# uknc_fdd2sd_rev1.net
KiCad netlist of a schematic drawn in EAGLE
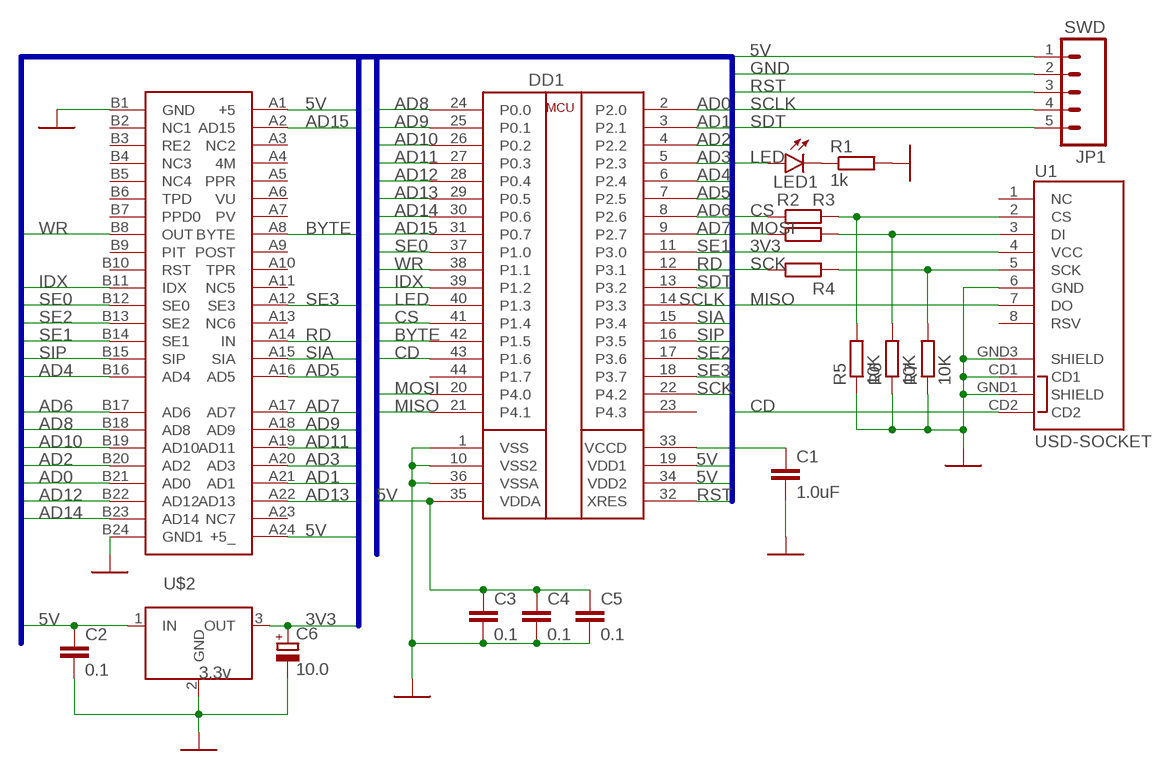
[diagram p0: schematic, sheet 1]

(export (version "E")
  (design (tool "Eeschema 10.0.6"))
  (components
    (comp (ref "C1")
      (value "1.0uF")
      (footprint "eagle-import:0805-CAP")
      (libsource (lib "eagle-import") (part "1.0UF-25V-+80/-20(0805){dblquote}"))
    )
    (comp (ref "C2")
      (value "0.1")
      (footprint "eagle-import:C0805")
      (libsource (lib "eagle-import") (part "C-EUC0805"))
    )
    (comp (ref "C3")
      (value "0.1")
      (footprint "eagle-import:C0805")
      (libsource (lib "eagle-import") (part "C-EUC0805"))
    )
    (comp (ref "C4")
      (value "0.1")
      (footprint "eagle-import:C0805")
      (libsource (lib "eagle-import") (part "C-EUC0805"))
    )
    (comp (ref "C5")
      (value "0.1")
      (footprint "eagle-import:C0805")
      (libsource (lib "eagle-import") (part "C-EUC0805"))
    )
    (comp (ref "C6")
      (value "10.0")
      (footprint "eagle-import:E1,8-4")
      (libsource (lib "eagle-import") (part "CPOL-EUE1.8-4"))
    )
    (comp (ref "DD1")
      (value "CY8C4245AXI")
      (footprint "eagle-import:TQFP-44")
      (libsource (lib "eagle-import") (part "CY8C4245AXI"))
    )
    (comp (ref "JP1")
      (value "SWD")
      (footprint "eagle-import:1X05")
      (libsource (lib "eagle-import") (part "M05PTH"))
    )
    (comp (ref "LED1")
      (value "LED1206")
      (footprint "eagle-import:LED-1206")
      (libsource (lib "eagle-import") (part "LED1206"))
    )
    (comp (ref "R1")
      (value "1k")
      (footprint "eagle-import:R0805")
      (libsource (lib "eagle-import") (part "R-EU_R0805"))
    )
    (comp (ref "R2")
      (value "R-EU_R0805")
      (footprint "eagle-import:R0805")
      (libsource (lib "eagle-import") (part "R-EU_R0805"))
    )
    (comp (ref "R3")
      (value "R-EU_R0805")
      (footprint "eagle-import:R0805")
      (libsource (lib "eagle-import") (part "R-EU_R0805"))
    )
    (comp (ref "R4")
      (value "R-EU_R0805")
      (footprint "eagle-import:R0805")
      (libsource (lib "eagle-import") (part "R-EU_R0805"))
    )
    (comp (ref "R5")
      (value "10K")
      (footprint "eagle-import:M0805")
      (libsource (lib "eagle-import") (part "R-EU_M0805"))
    )
    (comp (ref "R6")
      (value "10K")
      (footprint "eagle-import:M0805")
      (libsource (lib "eagle-import") (part "R-EU_M0805"))
    )
    (comp (ref "R7")
      (value "10K")
      (footprint "eagle-import:M0805")
      (libsource (lib "eagle-import") (part "R-EU_M0805"))
    )
    (comp (ref "U$1")
      (value "SNP")
      (footprint "eagle-import:SNP15-48-BOARD")
      (libsource (lib "eagle-import") (part "SNP"))
    )
    (comp (ref "U$2")
      (value "3.3v")
      (footprint "eagle-import:1235B")
      (libsource (lib "eagle-import") (part "1235B"))
    )
    (comp (ref "U1")
      (value "USD-SOCKET")
      (footprint "eagle-import:MICROSD_1_1")
      (libsource (lib "eagle-import") (part "USD-SOCKET"))
    )
  )
  (nets
    (net (code "1") (name "/3V3") (class "Default")
      (node (ref "C6") (pin "+") (pinfunction "+_+") (pintype "passive"))
      (node (ref "U$2") (pin "3") (pinfunction "OUT_3") (pintype "bidirectional"))
      (node (ref "U1") (pin "4") (pinfunction "VCC_4") (pintype "bidirectional"))
    )
    (net (code "2") (name "/5V") (class "Default")
      (node (ref "C2") (pin "1") (pinfunction "1_1") (pintype "passive"))
      (node (ref "C3") (pin "1") (pinfunction "1_1") (pintype "passive"))
      (node (ref "C4") (pin "1") (pinfunction "1_1") (pintype "passive"))
      (node (ref "C5") (pin "1") (pinfunction "1_1") (pintype "passive"))
      (node (ref "DD1") (pin "19") (pinfunction "VDD1_19") (pintype "bidirectional"))
      (node (ref "DD1") (pin "34") (pinfunction "VDD2_34") (pintype "bidirectional"))
      (node (ref "DD1") (pin "35") (pinfunction "VDDA_35") (pintype "bidirectional"))
      (node (ref "JP1") (pin "1") (pinfunction "1_1") (pintype "passive"))
      (node (ref "U$1") (pin "A1") (pinfunction "+5_A1") (pintype "bidirectional"))
      (node (ref "U$1") (pin "A24") (pinfunction "+5__A24") (pintype "bidirectional"))
      (node (ref "U$2") (pin "1") (pinfunction "IN_1") (pintype "bidirectional"))
    )
    (net (code "3") (name "/AD0") (class "Default")
      (node (ref "DD1") (pin "2") (pinfunction "P2.0_2") (pintype "bidirectional"))
      (node (ref "U$1") (pin "B21") (pinfunction "AD0_B21") (pintype "bidirectional"))
    )
    (net (code "4") (name "/AD1") (class "Default")
      (node (ref "DD1") (pin "3") (pinfunction "P2.1_3") (pintype "bidirectional"))
      (node (ref "U$1") (pin "A21") (pinfunction "AD1_A21") (pintype "bidirectional"))
    )
    (net (code "5") (name "/AD2") (class "Default")
      (node (ref "DD1") (pin "4") (pinfunction "P2.2_4") (pintype "bidirectional"))
      (node (ref "U$1") (pin "B20") (pinfunction "AD2_B20") (pintype "bidirectional"))
    )
    (net (code "6") (name "/AD3") (class "Default")
      (node (ref "DD1") (pin "5") (pinfunction "P2.3_5") (pintype "bidirectional"))
      (node (ref "U$1") (pin "A20") (pinfunction "AD3_A20") (pintype "bidirectional"))
    )
    (net (code "7") (name "/AD4") (class "Default")
      (node (ref "DD1") (pin "6") (pinfunction "P2.4_6") (pintype "bidirectional"))
      (node (ref "U$1") (pin "B16") (pinfunction "AD4_B16") (pintype "bidirectional"))
    )
    (net (code "8") (name "/AD5") (class "Default")
      (node (ref "DD1") (pin "7") (pinfunction "P2.5_7") (pintype "bidirectional"))
      (node (ref "U$1") (pin "A16") (pinfunction "AD5_A16") (pintype "bidirectional"))
    )
    (net (code "9") (name "/AD6") (class "Default")
      (node (ref "DD1") (pin "8") (pinfunction "P2.6_8") (pintype "bidirectional"))
      (node (ref "U$1") (pin "B17") (pinfunction "AD6_B17") (pintype "bidirectional"))
    )
    (net (code "10") (name "/AD7") (class "Default")
      (node (ref "DD1") (pin "9") (pinfunction "P2.7_9") (pintype "bidirectional"))
      (node (ref "U$1") (pin "A17") (pinfunction "AD7_A17") (pintype "bidirectional"))
    )
    (net (code "11") (name "/AD8") (class "Default")
      (node (ref "DD1") (pin "24") (pinfunction "P0.0_24") (pintype "bidirectional"))
      (node (ref "U$1") (pin "B18") (pinfunction "AD8_B18") (pintype "bidirectional"))
    )
    (net (code "12") (name "/AD9") (class "Default")
      (node (ref "DD1") (pin "25") (pinfunction "P0.1_25") (pintype "bidirectional"))
      (node (ref "U$1") (pin "A18") (pinfunction "AD9_A18") (pintype "bidirectional"))
    )
    (net (code "13") (name "/AD10") (class "Default")
      (node (ref "DD1") (pin "26") (pinfunction "P0.2_26") (pintype "bidirectional"))
      (node (ref "U$1") (pin "B19") (pinfunction "AD10_B19") (pintype "bidirectional"))
    )
    (net (code "14") (name "/AD11") (class "Default")
      (node (ref "DD1") (pin "27") (pinfunction "P0.3_27") (pintype "bidirectional"))
      (node (ref "U$1") (pin "A19") (pinfunction "AD11_A19") (pintype "bidirectional"))
    )
    (net (code "15") (name "/AD12") (class "Default")
      (node (ref "DD1") (pin "28") (pinfunction "P0.4_28") (pintype "bidirectional"))
      (node (ref "U$1") (pin "B22") (pinfunction "AD12_B22") (pintype "bidirectional"))
    )
    (net (code "16") (name "/AD13") (class "Default")
      (node (ref "DD1") (pin "29") (pinfunction "P0.5_29") (pintype "bidirectional"))
      (node (ref "U$1") (pin "A22") (pinfunction "AD13_A22") (pintype "bidirectional"))
    )
    (net (code "17") (name "/AD14") (class "Default")
      (node (ref "DD1") (pin "30") (pinfunction "P0.6_30") (pintype "bidirectional"))
      (node (ref "U$1") (pin "B23") (pinfunction "AD14_B23") (pintype "bidirectional"))
    )
    (net (code "18") (name "/AD15") (class "Default")
      (node (ref "DD1") (pin "31") (pinfunction "P0.7_31") (pintype "bidirectional"))
      (node (ref "U$1") (pin "A2") (pinfunction "AD15_A2") (pintype "bidirectional"))
    )
    (net (code "19") (name "/BYTE") (class "Default")
      (node (ref "DD1") (pin "42") (pinfunction "P1.5_42") (pintype "bidirectional"))
      (node (ref "U$1") (pin "A8") (pinfunction "BYTE_A8") (pintype "bidirectional"))
    )
    (net (code "20") (name "/CD") (class "Default")
      (node (ref "DD1") (pin "43") (pinfunction "P1.6_43") (pintype "bidirectional"))
      (node (ref "U1") (pin "CD2") (pinfunction "CD2_CD2") (pintype "bidirectional"))
    )
    (net (code "21") (name "/CS") (class "Default")
      (node (ref "DD1") (pin "41") (pinfunction "P1.4_41") (pintype "bidirectional"))
      (node (ref "R2") (pin "1") (pinfunction "1_1") (pintype "passive"))
    )
    (net (code "22") (name "/IDX") (class "Default")
      (node (ref "DD1") (pin "39") (pinfunction "P1.2_39") (pintype "bidirectional"))
      (node (ref "U$1") (pin "B11") (pinfunction "IDX_B11") (pintype "bidirectional"))
    )
    (net (code "23") (name "/LED") (class "Default")
      (node (ref "DD1") (pin "40") (pinfunction "P1.3_40") (pintype "bidirectional"))
      (node (ref "LED1") (pin "A") (pinfunction "A_A") (pintype "passive"))
    )
    (net (code "24") (name "/MISO") (class "Default")
      (node (ref "DD1") (pin "21") (pinfunction "P4.1_21") (pintype "bidirectional"))
      (node (ref "U1") (pin "7") (pinfunction "DO_7") (pintype "bidirectional"))
    )
    (net (code "25") (name "/MOSI") (class "Default")
      (node (ref "DD1") (pin "20") (pinfunction "P4.0_20") (pintype "bidirectional"))
      (node (ref "R3") (pin "1") (pinfunction "1_1") (pintype "passive"))
    )
    (net (code "26") (name "/RD") (class "Default")
      (node (ref "DD1") (pin "12") (pinfunction "P3.1_12") (pintype "bidirectional"))
      (node (ref "U$1") (pin "A14") (pinfunction "IN_A14") (pintype "bidirectional"))
    )
    (net (code "27") (name "/RST") (class "Default")
      (node (ref "DD1") (pin "32") (pinfunction "XRES_32") (pintype "bidirectional"))
      (node (ref "JP1") (pin "3") (pinfunction "3_3") (pintype "passive"))
    )
    (net (code "28") (name "/SCK") (class "Default")
      (node (ref "DD1") (pin "22") (pinfunction "P4.2_22") (pintype "bidirectional"))
      (node (ref "R4") (pin "1") (pinfunction "1_1") (pintype "passive"))
    )
    (net (code "29") (name "/SCLK") (class "Default")
      (node (ref "DD1") (pin "14") (pinfunction "P3.3_14") (pintype "bidirectional"))
      (node (ref "JP1") (pin "4") (pinfunction "4_4") (pintype "passive"))
    )
    (net (code "30") (name "/SDT") (class "Default")
      (node (ref "DD1") (pin "13") (pinfunction "P3.2_13") (pintype "bidirectional"))
      (node (ref "JP1") (pin "5") (pinfunction "5_5") (pintype "passive"))
    )
    (net (code "31") (name "/SE0") (class "Default")
      (node (ref "DD1") (pin "37") (pinfunction "P1.0_37") (pintype "bidirectional"))
      (node (ref "U$1") (pin "B12") (pinfunction "SE0_B12") (pintype "bidirectional"))
    )
    (net (code "32") (name "/SE1") (class "Default")
      (node (ref "DD1") (pin "11") (pinfunction "P3.0_11") (pintype "bidirectional"))
      (node (ref "U$1") (pin "B14") (pinfunction "SE1_B14") (pintype "bidirectional"))
    )
    (net (code "33") (name "/SE2") (class "Default")
      (node (ref "DD1") (pin "17") (pinfunction "P3.6_17") (pintype "bidirectional"))
      (node (ref "U$1") (pin "B13") (pinfunction "SE2_B13") (pintype "bidirectional"))
    )
    (net (code "34") (name "/SE3") (class "Default")
      (node (ref "DD1") (pin "18") (pinfunction "P3.7_18") (pintype "bidirectional"))
      (node (ref "U$1") (pin "A12") (pinfunction "SE3_A12") (pintype "bidirectional"))
    )
    (net (code "35") (name "/SIA") (class "Default")
      (node (ref "DD1") (pin "15") (pinfunction "P3.4_15") (pintype "bidirectional"))
      (node (ref "U$1") (pin "A15") (pinfunction "SIA_A15") (pintype "bidirectional"))
    )
    (net (code "36") (name "/SIP") (class "Default")
      (node (ref "DD1") (pin "16") (pinfunction "P3.5_16") (pintype "bidirectional"))
      (node (ref "U$1") (pin "B15") (pinfunction "SIP_B15") (pintype "bidirectional"))
    )
    (net (code "37") (name "/WR") (class "Default")
      (node (ref "DD1") (pin "38") (pinfunction "P1.1_38") (pintype "bidirectional"))
      (node (ref "U$1") (pin "B8") (pinfunction "OUT_B8") (pintype "bidirectional"))
    )
    (net (code "38") (name "GND") (class "Default")
      (node (ref "C1") (pin "2") (pinfunction "2_2") (pintype "passive"))
      (node (ref "C2") (pin "2") (pinfunction "2_2") (pintype "passive"))
      (node (ref "C3") (pin "2") (pinfunction "2_2") (pintype "passive"))
      (node (ref "C4") (pin "2") (pinfunction "2_2") (pintype "passive"))
      (node (ref "C5") (pin "2") (pinfunction "2_2") (pintype "passive"))
      (node (ref "C6") (pin "-") (pinfunction "-_-") (pintype "passive"))
      (node (ref "DD1") (pin "1") (pinfunction "VSS_1") (pintype "bidirectional"))
      (node (ref "DD1") (pin "10") (pinfunction "VSS2_10") (pintype "bidirectional"))
      (node (ref "DD1") (pin "36") (pinfunction "VSSA_36") (pintype "bidirectional"))
      (node (ref "JP1") (pin "2") (pinfunction "2_2") (pintype "passive"))
      (node (ref "R1") (pin "2") (pinfunction "2_2") (pintype "passive"))
      (node (ref "R5") (pin "1") (pinfunction "1_1") (pintype "passive"))
      (node (ref "R6") (pin "1") (pinfunction "1_1") (pintype "passive"))
      (node (ref "R7") (pin "1") (pinfunction "1_1") (pintype "passive"))
      (node (ref "U$1") (pin "B1") (pinfunction "GND_B1") (pintype "bidirectional"))
      (node (ref "U$1") (pin "B24") (pinfunction "GND1_B24") (pintype "bidirectional"))
      (node (ref "U$2") (pin "2") (pinfunction "GND_2") (pintype "bidirectional"))
      (node (ref "U1") (pin "6") (pinfunction "GND_6") (pintype "bidirectional"))
      (node (ref "U1") (pin "CD1") (pinfunction "CD1_CD1") (pintype "bidirectional"))
      (node (ref "U1") (pin "GND1") (pinfunction "SHIELD_GND1") (pintype "bidirectional"))
      (node (ref "U1") (pin "GND3") (pinfunction "SHIELD_GND3") (pintype "bidirectional"))
    )
    (net (code "39") (name "Net-(DD1-VCCD)") (class "Default")
      (node (ref "C1") (pin "1") (pinfunction "1_1") (pintype "passive"))
      (node (ref "DD1") (pin "33") (pinfunction "VCCD_33") (pintype "bidirectional"))
    )
    (net (code "40") (name "Net-(LED1-PadC)") (class "Default")
      (node (ref "LED1") (pin "C") (pinfunction "C_C") (pintype "passive"))
      (node (ref "R1") (pin "1") (pinfunction "1_1") (pintype "passive"))
    )
    (net (code "41") (name "Net-(U1-CS)") (class "Default")
      (node (ref "R2") (pin "2") (pinfunction "2_2") (pintype "passive"))
      (node (ref "R5") (pin "2") (pinfunction "2_2") (pintype "passive"))
      (node (ref "U1") (pin "2") (pinfunction "CS_2") (pintype "bidirectional"))
    )
    (net (code "42") (name "Net-(U1-DI)") (class "Default")
      (node (ref "R3") (pin "2") (pinfunction "2_2") (pintype "passive"))
      (node (ref "R6") (pin "2") (pinfunction "2_2") (pintype "passive"))
      (node (ref "U1") (pin "3") (pinfunction "DI_3") (pintype "bidirectional"))
    )
    (net (code "43") (name "Net-(U1-SCK)") (class "Default")
      (node (ref "R4") (pin "2") (pinfunction "2_2") (pintype "passive"))
      (node (ref "R7") (pin "2") (pinfunction "2_2") (pintype "passive"))
      (node (ref "U1") (pin "5") (pinfunction "SCK_5") (pintype "bidirectional"))
    )
    (net (code "44") (name "unconnected-(DD1-P1.7-Pad44)") (class "Default")
      (node (ref "DD1") (pin "44") (pinfunction "P1.7_44") (pintype "bidirectional"))
    )
    (net (code "45") (name "unconnected-(DD1-P4.3-Pad23)") (class "Default")
      (node (ref "DD1") (pin "23") (pinfunction "P4.3_23") (pintype "bidirectional"))
    )
    (net (code "46") (name "unconnected-(U$1-4M-PadA4)") (class "Default")
      (node (ref "U$1") (pin "A4") (pinfunction "4M_A4") (pintype "bidirectional"))
    )
    (net (code "47") (name "unconnected-(U$1-NC1-PadB2)") (class "Default")
      (node (ref "U$1") (pin "B2") (pinfunction "NC1_B2") (pintype "bidirectional"))
    )
    (net (code "48") (name "unconnected-(U$1-NC2-PadA3)") (class "Default")
      (node (ref "U$1") (pin "A3") (pinfunction "NC2_A3") (pintype "bidirectional"))
    )
    (net (code "49") (name "unconnected-(U$1-NC3-PadB4)") (class "Default")
      (node (ref "U$1") (pin "B4") (pinfunction "NC3_B4") (pintype "bidirectional"))
    )
    (net (code "50") (name "unconnected-(U$1-NC4-PadB5)") (class "Default")
      (node (ref "U$1") (pin "B5") (pinfunction "NC4_B5") (pintype "bidirectional"))
    )
    (net (code "51") (name "unconnected-(U$1-NC5-PadA11)") (class "Default")
      (node (ref "U$1") (pin "A11") (pinfunction "NC5_A11") (pintype "bidirectional"))
    )
    (net (code "52") (name "unconnected-(U$1-NC6-PadA13)") (class "Default")
      (node (ref "U$1") (pin "A13") (pinfunction "NC6_A13") (pintype "bidirectional"))
    )
    (net (code "53") (name "unconnected-(U$1-NC7-PadA23)") (class "Default")
      (node (ref "U$1") (pin "A23") (pinfunction "NC7_A23") (pintype "bidirectional"))
    )
    (net (code "54") (name "unconnected-(U$1-PIT-PadB9)") (class "Default")
      (node (ref "U$1") (pin "B9") (pinfunction "PIT_B9") (pintype "bidirectional"))
    )
    (net (code "55") (name "unconnected-(U$1-POST-PadA9)") (class "Default")
      (node (ref "U$1") (pin "A9") (pinfunction "POST_A9") (pintype "bidirectional"))
    )
    (net (code "56") (name "unconnected-(U$1-PPD0-PadB7)") (class "Default")
      (node (ref "U$1") (pin "B7") (pinfunction "PPD0_B7") (pintype "bidirectional"))
    )
    (net (code "57") (name "unconnected-(U$1-PPR-PadA5)") (class "Default")
      (node (ref "U$1") (pin "A5") (pinfunction "PPR_A5") (pintype "bidirectional"))
    )
    (net (code "58") (name "unconnected-(U$1-PV-PadA7)") (class "Default")
      (node (ref "U$1") (pin "A7") (pinfunction "PV_A7") (pintype "bidirectional"))
    )
    (net (code "59") (name "unconnected-(U$1-RE2-PadB3)") (class "Default")
      (node (ref "U$1") (pin "B3") (pinfunction "RE2_B3") (pintype "bidirectional"))
    )
    (net (code "60") (name "unconnected-(U$1-RST-PadB10)") (class "Default")
      (node (ref "U$1") (pin "B10") (pinfunction "RST_B10") (pintype "bidirectional"))
    )
    (net (code "61") (name "unconnected-(U$1-TPD-PadB6)") (class "Default")
      (node (ref "U$1") (pin "B6") (pinfunction "TPD_B6") (pintype "bidirectional"))
    )
    (net (code "62") (name "unconnected-(U$1-TPR-PadA10)") (class "Default")
      (node (ref "U$1") (pin "A10") (pinfunction "TPR_A10") (pintype "bidirectional"))
    )
    (net (code "63") (name "unconnected-(U$1-VU-PadA6)") (class "Default")
      (node (ref "U$1") (pin "A6") (pinfunction "VU_A6") (pintype "bidirectional"))
    )
    (net (code "64") (name "unconnected-(U1-NC-Pad1)") (class "Default")
      (node (ref "U1") (pin "1") (pinfunction "NC_1") (pintype "bidirectional"))
    )
    (net (code "65") (name "unconnected-(U1-RSV-Pad8)") (class "Default")
      (node (ref "U1") (pin "8") (pinfunction "RSV_8") (pintype "bidirectional"))
    )
  )
)
